# cytron-1.net
KiCad netlist of a schematic drawn in EAGLE
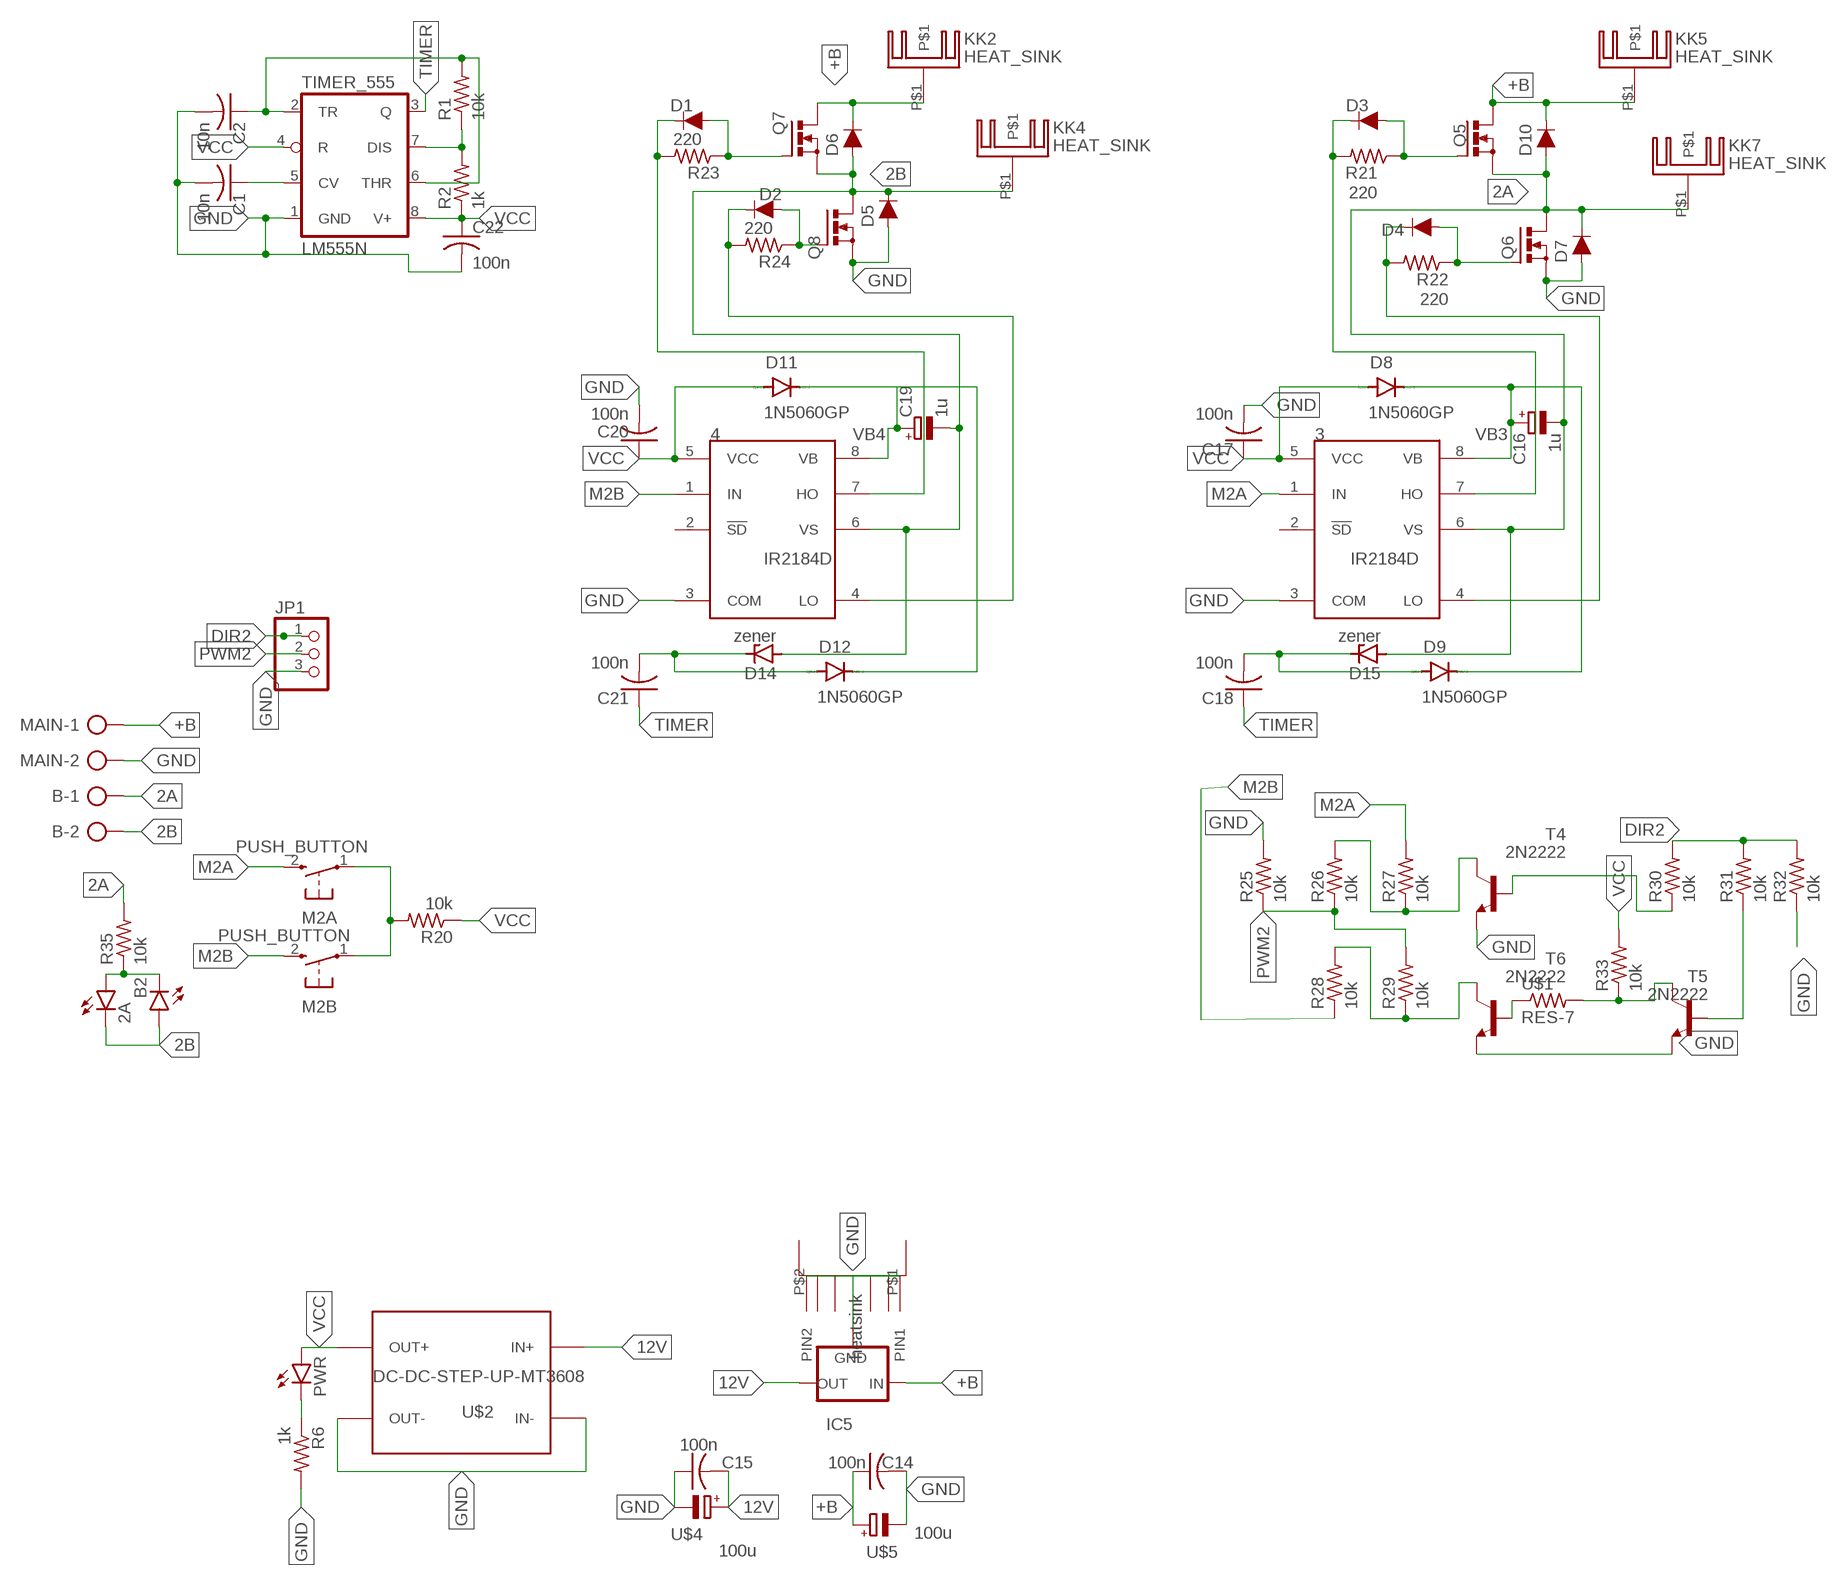
[diagram p0: schematic, sheet 1]

(export (version "E")
  (design (tool "Eeschema 10.0.6"))
  (components
    (comp (ref "2A")
      (value "LED3MM")
      (footprint "eagle-import:LED3MM")
      (libsource (lib "eagle-import") (part "LED3MM"))
    )
    (comp (ref "3")
      (value "IR2184D")
      (footprint "eagle-import:DIL08")
      (libsource (lib "eagle-import") (part "IR2184D"))
    )
    (comp (ref "4")
      (value "IR2184D")
      (footprint "eagle-import:DIL08")
      (libsource (lib "eagle-import") (part "IR2184D"))
    )
    (comp (ref "B")
      (value "ROSTA.POWER")
      (footprint "eagle-import:W239-302")
      (libsource (lib "eagle-import") (part "ROSTA.POWER"))
    )
    (comp (ref "B2")
      (value "LED3MM")
      (footprint "eagle-import:LED3MM")
      (libsource (lib "eagle-import") (part "LED3MM"))
    )
    (comp (ref "C1")
      (value "10n")
      (footprint "eagle-import:C025-025X050")
      (libsource (lib "eagle-import") (part "C-US025-025X050"))
    )
    (comp (ref "C2")
      (value "10n")
      (footprint "eagle-import:C025-025X050")
      (libsource (lib "eagle-import") (part "C-US025-025X050"))
    )
    (comp (ref "C14")
      (value "100n")
      (footprint "eagle-import:C025-025X050")
      (libsource (lib "eagle-import") (part "C-US025-025X050"))
    )
    (comp (ref "C15")
      (value "100n")
      (footprint "eagle-import:C025-025X050")
      (libsource (lib "eagle-import") (part "C-US025-025X050"))
    )
    (comp (ref "C16")
      (value "1u")
      (footprint "eagle-import:E5-5")
      (libsource (lib "eagle-import") (part "CPOL-EUE5-5"))
    )
    (comp (ref "C17")
      (value "100n")
      (footprint "eagle-import:C025-025X050")
      (libsource (lib "eagle-import") (part "C-US025-025X050"))
    )
    (comp (ref "C18")
      (value "100n")
      (footprint "eagle-import:C025-025X050")
      (libsource (lib "eagle-import") (part "C-US025-025X050"))
    )
    (comp (ref "C19")
      (value "1u")
      (footprint "eagle-import:E5-5")
      (libsource (lib "eagle-import") (part "CPOL-EUE5-5"))
    )
    (comp (ref "C20")
      (value "100n")
      (footprint "eagle-import:C025-025X050")
      (libsource (lib "eagle-import") (part "C-US025-025X050"))
    )
    (comp (ref "C21")
      (value "100n")
      (footprint "eagle-import:C025-025X050")
      (libsource (lib "eagle-import") (part "C-US025-025X050"))
    )
    (comp (ref "C22")
      (value "100n")
      (footprint "eagle-import:C025-025X050")
      (libsource (lib "eagle-import") (part "C-US025-025X050"))
    )
    (comp (ref "D1")
      (value "1A/50V/1.1V")
      (footprint "eagle-import:DIODE-1N4001")
      (libsource (lib "eagle-import") (part "DIODE(1A)-PTH"))
    )
    (comp (ref "D2")
      (value "1A/50V/1.1V")
      (footprint "eagle-import:DIODE-1N4001")
      (libsource (lib "eagle-import") (part "DIODE(1A)-PTH"))
    )
    (comp (ref "D3")
      (value "1A/50V/1.1V")
      (footprint "eagle-import:DIODE-1N4001")
      (libsource (lib "eagle-import") (part "DIODE(1A)-PTH"))
    )
    (comp (ref "D4")
      (value "1A/50V/1.1V")
      (footprint "eagle-import:DIODE-1N4001")
      (libsource (lib "eagle-import") (part "DIODE(1A)-PTH"))
    )
    (comp (ref "D5")
      (value "1A/50V/1.1V")
      (footprint "eagle-import:DIODE-1N4001")
      (libsource (lib "eagle-import") (part "DIODE(1A)-PTH"))
    )
    (comp (ref "D6")
      (value "1A/50V/1.1V")
      (footprint "eagle-import:DIODE-1N4001")
      (libsource (lib "eagle-import") (part "DIODE(1A)-PTH"))
    )
    (comp (ref "D7")
      (value "1A/50V/1.1V")
      (footprint "eagle-import:DIODE-1N4001")
      (libsource (lib "eagle-import") (part "DIODE(1A)-PTH"))
    )
    (comp (ref "D8")
      (value "1N5060GP")
      (footprint "eagle-import:DO15-12")
      (libsource (lib "eagle-import") (part "1N5060GP"))
    )
    (comp (ref "D9")
      (value "1N5060GP")
      (footprint "eagle-import:DO15-12")
      (libsource (lib "eagle-import") (part "1N5060GP"))
    )
    (comp (ref "D10")
      (value "1A/50V/1.1V")
      (footprint "eagle-import:DIODE-1N4001")
      (libsource (lib "eagle-import") (part "DIODE(1A)-PTH"))
    )
    (comp (ref "D11")
      (value "1N5060GP")
      (footprint "eagle-import:DO15-12")
      (libsource (lib "eagle-import") (part "1N5060GP"))
    )
    (comp (ref "D12")
      (value "1N5060GP")
      (footprint "eagle-import:DO15-12")
      (libsource (lib "eagle-import") (part "1N5060GP"))
    )
    (comp (ref "D14")
      (value "zener")
      (footprint "eagle-import:SOD81")
      (libsource (lib "eagle-import") (part "BZD23"))
    )
    (comp (ref "D15")
      (value "zener")
      (footprint "eagle-import:SOD81")
      (libsource (lib "eagle-import") (part "BZD23"))
    )
    (comp (ref "IC5")
      (value "78XXL")
      (footprint "eagle-import:78XXL")
      (libsource (lib "eagle-import") (part "78XXL"))
    )
    (comp (ref "JP1")
      (value "PINHD-3_DATA")
      (footprint "eagle-import:1X03_DATA")
      (libsource (lib "eagle-import") (part "PINHD-3_DATA"))
    )
    (comp (ref "KK2")
      (value "HEAT_SINK")
      (footprint "eagle-import:SK95-2M3")
      (libsource (lib "eagle-import") (part "HEAT_SINK"))
    )
    (comp (ref "KK4")
      (value "HEAT_SINK")
      (footprint "eagle-import:SK95-2M3")
      (libsource (lib "eagle-import") (part "HEAT_SINK"))
    )
    (comp (ref "KK5")
      (value "HEAT_SINK")
      (footprint "eagle-import:SK95-2M3")
      (libsource (lib "eagle-import") (part "HEAT_SINK"))
    )
    (comp (ref "KK7")
      (value "HEAT_SINK")
      (footprint "eagle-import:SK95-2M3")
      (libsource (lib "eagle-import") (part "HEAT_SINK"))
    )
    (comp (ref "M2A")
      (value "PUSH_BUTTON")
      (footprint "eagle-import:B3F-10XX")
      (libsource (lib "eagle-import") (part "PUSH_BUTTON"))
    )
    (comp (ref "M2B")
      (value "PUSH_BUTTON")
      (footprint "eagle-import:B3F-10XX")
      (libsource (lib "eagle-import") (part "PUSH_BUTTON"))
    )
    (comp (ref "MAIN")
      (value "ROSTA.POWER")
      (footprint "eagle-import:W239-302")
      (libsource (lib "eagle-import") (part "ROSTA.POWER"))
    )
    (comp (ref "PWR")
      (value "LED5MM")
      (footprint "eagle-import:LED5MM")
      (libsource (lib "eagle-import") (part "LED5MM"))
    )
    (comp (ref "Q5")
      (value "MOSFET_NTO220BV")
      (footprint "eagle-import:TO220BV")
      (libsource (lib "eagle-import") (part "MOSFET_NTO220BV"))
    )
    (comp (ref "Q6")
      (value "MOSFET_NTO220BV")
      (footprint "eagle-import:TO220BV")
      (libsource (lib "eagle-import") (part "MOSFET_NTO220BV"))
    )
    (comp (ref "Q7")
      (value "MOSFET_NTO220BV")
      (footprint "eagle-import:TO220BV")
      (libsource (lib "eagle-import") (part "MOSFET_NTO220BV"))
    )
    (comp (ref "Q8")
      (value "MOSFET_NTO220BV")
      (footprint "eagle-import:TO220BV")
      (libsource (lib "eagle-import") (part "MOSFET_NTO220BV"))
    )
    (comp (ref "R1")
      (value "10k")
      (footprint "eagle-import:0204_7")
      (libsource (lib "eagle-import") (part "R-US_0204/7"))
    )
    (comp (ref "R2")
      (value "1k")
      (footprint "eagle-import:0204_7")
      (libsource (lib "eagle-import") (part "R-US_0204/7"))
    )
    (comp (ref "R6")
      (value "1k")
      (footprint "eagle-import:0204_7")
      (libsource (lib "eagle-import") (part "R-US_0204/7"))
    )
    (comp (ref "R20")
      (value "10k")
      (footprint "eagle-import:0204_7")
      (libsource (lib "eagle-import") (part "R-US_0204/7"))
    )
    (comp (ref "R21")
      (value "220")
      (footprint "eagle-import:0204_7")
      (libsource (lib "eagle-import") (part "R-US_0204/7"))
    )
    (comp (ref "R22")
      (value "220")
      (footprint "eagle-import:0204_7")
      (libsource (lib "eagle-import") (part "R-US_0204/7"))
    )
    (comp (ref "R23")
      (value "220")
      (footprint "eagle-import:0204_7")
      (libsource (lib "eagle-import") (part "R-US_0204/7"))
    )
    (comp (ref "R24")
      (value "220")
      (footprint "eagle-import:0204_7")
      (libsource (lib "eagle-import") (part "R-US_0204/7"))
    )
    (comp (ref "R25")
      (value "10k")
      (footprint "eagle-import:0204_7")
      (libsource (lib "eagle-import") (part "R-US_0204/7"))
    )
    (comp (ref "R26")
      (value "10k")
      (footprint "eagle-import:0204_7")
      (libsource (lib "eagle-import") (part "R-US_0204/7"))
    )
    (comp (ref "R27")
      (value "10k")
      (footprint "eagle-import:0204_7")
      (libsource (lib "eagle-import") (part "R-US_0204/7"))
    )
    (comp (ref "R28")
      (value "10k")
      (footprint "eagle-import:0204_7")
      (libsource (lib "eagle-import") (part "R-US_0204/7"))
    )
    (comp (ref "R29")
      (value "10k")
      (footprint "eagle-import:0204_7")
      (libsource (lib "eagle-import") (part "R-US_0204/7"))
    )
    (comp (ref "R30")
      (value "10k")
      (footprint "eagle-import:0204_7")
      (libsource (lib "eagle-import") (part "R-US_0204/7"))
    )
    (comp (ref "R31")
      (value "10k")
      (footprint "eagle-import:0204_7")
      (libsource (lib "eagle-import") (part "R-US_0204/7"))
    )
    (comp (ref "R32")
      (value "10k")
      (footprint "eagle-import:0204_7")
      (libsource (lib "eagle-import") (part "R-US_0204/7"))
    )
    (comp (ref "R33")
      (value "10k")
      (footprint "eagle-import:0204_7")
      (libsource (lib "eagle-import") (part "R-US_0204/7"))
    )
    (comp (ref "R35")
      (value "10k")
      (footprint "eagle-import:0204_7")
      (libsource (lib "eagle-import") (part "R-US_0204/7"))
    )
    (comp (ref "T4")
      (value "2N2222")
      (footprint "eagle-import:TO18")
      (fields (field (name "SPICEPREFIX") "J"))
      (libsource (lib "eagle-import") (part "2N2222"))
    )
    (comp (ref "T5")
      (value "2N2222")
      (footprint "eagle-import:TO18")
      (fields (field (name "SPICEPREFIX") "J"))
      (libsource (lib "eagle-import") (part "2N2222"))
    )
    (comp (ref "T6")
      (value "2N2222")
      (footprint "eagle-import:TO18")
      (fields (field (name "SPICEPREFIX") "J"))
      (libsource (lib "eagle-import") (part "2N2222"))
    )
    (comp (ref "TIMER_555")
      (value "LM555N")
      (footprint "eagle-import:DIL08")
      (libsource (lib "eagle-import") (part "555NLM"))
    )
    (comp (ref "U$1")
      (value "RES-7")
      (footprint "eagle-import:0204_7")
      (fields (field (name "SPICEPREFIX") "B"))
      (libsource (lib "eagle-import") (part "RES-7"))
    )
    (comp (ref "U$2")
      (value "DC-DC-STEP-UP-MT3608")
      (footprint "eagle-import:DC-DC-STEP-UP-MT3608")
      (libsource (lib "eagle-import") (part "DC-DC-STEP-UP-MT3608"))
    )
    (comp (ref "U$3")
      (value "HEAT-SINK")
      (footprint "eagle-import:HEAT_SINK")
      (libsource (lib "eagle-import") (part "HEAT-SINK"))
    )
    (comp (ref "U$4")
      (value "100u")
      (footprint "eagle-import:E3,5-8")
      (libsource (lib "eagle-import") (part "CAP_POL"))
    )
    (comp (ref "U$5")
      (value "100u")
      (footprint "eagle-import:E3,5-8")
      (libsource (lib "eagle-import") (part "CAP_POL"))
    )
  )
  (nets
    (net (code "1") (name "+B") (class "Default")
      (node (ref "C14") (pin "1") (pinfunction "1_1") (pintype "passive"))
      (node (ref "D10") (pin "C") (pinfunction "C_C") (pintype "passive"))
      (node (ref "D6") (pin "C") (pinfunction "C_C") (pintype "passive"))
      (node (ref "IC5") (pin "IN") (pinfunction "IN_IN") (pintype "input"))
      (node (ref "KK2") (pin "P$1") (pinfunction "P$1_P$1") (pintype "bidirectional"))
      (node (ref "KK5") (pin "P$1") (pinfunction "P$1_P$1") (pintype "bidirectional"))
      (node (ref "MAIN") (pin "1") (pinfunction "KL_1") (pintype "passive"))
      (node (ref "Q5") (pin "D") (pinfunction "D_D") (pintype "passive"))
      (node (ref "Q7") (pin "D") (pinfunction "D_D") (pintype "passive"))
      (node (ref "U$5") (pin "+") (pinfunction "+_+") (pintype "passive"))
    )
    (net (code "2") (name "/VB3") (class "Default")
      (node (ref "3") (pin "8") (pinfunction "VB_8") (pintype "power_in"))
      (node (ref "C16") (pin "+") (pinfunction "+_+") (pintype "passive"))
      (node (ref "D8") (pin "C") (pinfunction "C_C") (pintype "passive"))
      (node (ref "D9") (pin "C") (pinfunction "C_C") (pintype "passive"))
    )
    (net (code "3") (name "/VB4") (class "Default")
      (node (ref "4") (pin "8") (pinfunction "VB_8") (pintype "power_in"))
      (node (ref "C19") (pin "+") (pinfunction "+_+") (pintype "passive"))
      (node (ref "D11") (pin "C") (pinfunction "C_C") (pintype "passive"))
      (node (ref "D12") (pin "C") (pinfunction "C_C") (pintype "passive"))
    )
    (net (code "4") (name "2A") (class "Default")
      (node (ref "3") (pin "6") (pinfunction "VS_6") (pintype "power_in"))
      (node (ref "B") (pin "1") (pinfunction "KL_1") (pintype "passive"))
      (node (ref "C16") (pin "-") (pinfunction "-_-") (pintype "passive"))
      (node (ref "D10") (pin "A") (pinfunction "A_A") (pintype "passive"))
      (node (ref "D15") (pin "A") (pinfunction "A_A") (pintype "passive"))
      (node (ref "D7") (pin "C") (pinfunction "C_C") (pintype "passive"))
      (node (ref "KK7") (pin "P$1") (pinfunction "P$1_P$1") (pintype "bidirectional"))
      (node (ref "Q5") (pin "S") (pinfunction "S_S") (pintype "passive"))
      (node (ref "Q6") (pin "D") (pinfunction "D_D") (pintype "passive"))
      (node (ref "R35") (pin "2") (pinfunction "2_2") (pintype "passive"))
    )
    (net (code "5") (name "2B") (class "Default")
      (node (ref "2A") (pin "K") (pinfunction "C_K") (pintype "passive"))
      (node (ref "4") (pin "6") (pinfunction "VS_6") (pintype "power_in"))
      (node (ref "B") (pin "2") (pinfunction "KL_2") (pintype "passive"))
      (node (ref "B2") (pin "A") (pinfunction "A_A") (pintype "passive"))
      (node (ref "C19") (pin "-") (pinfunction "-_-") (pintype "passive"))
      (node (ref "D14") (pin "A") (pinfunction "A_A") (pintype "passive"))
      (node (ref "D5") (pin "C") (pinfunction "C_C") (pintype "passive"))
      (node (ref "D6") (pin "A") (pinfunction "A_A") (pintype "passive"))
      (node (ref "KK4") (pin "P$1") (pinfunction "P$1_P$1") (pintype "bidirectional"))
      (node (ref "Q7") (pin "S") (pinfunction "S_S") (pintype "passive"))
      (node (ref "Q8") (pin "D") (pinfunction "D_D") (pintype "passive"))
    )
    (net (code "6") (name "12V") (class "Default")
      (node (ref "C15") (pin "2") (pinfunction "2_2") (pintype "passive"))
      (node (ref "IC5") (pin "OUT") (pinfunction "OUT_OUT") (pintype "passive"))
      (node (ref "U$2") (pin "IN+") (pinfunction "IN+_IN+") (pintype "bidirectional"))
      (node (ref "U$4") (pin "+") (pinfunction "+_+") (pintype "passive"))
    )
    (net (code "7") (name "DIR2") (class "Default")
      (node (ref "JP1") (pin "1") (pinfunction "1_1") (pintype "passive"))
      (node (ref "R30") (pin "2") (pinfunction "2_2") (pintype "passive"))
      (node (ref "R31") (pin "2") (pinfunction "2_2") (pintype "passive"))
      (node (ref "R32") (pin "2") (pinfunction "2_2") (pintype "passive"))
    )
    (net (code "8") (name "GND") (class "Default")
      (node (ref "3") (pin "3") (pinfunction "COM_3") (pintype "power_in"))
      (node (ref "4") (pin "3") (pinfunction "COM_3") (pintype "power_in"))
      (node (ref "C1") (pin "2") (pinfunction "2_2") (pintype "passive"))
      (node (ref "C14") (pin "2") (pinfunction "2_2") (pintype "passive"))
      (node (ref "C15") (pin "1") (pinfunction "1_1") (pintype "passive"))
      (node (ref "C17") (pin "2") (pinfunction "2_2") (pintype "passive"))
      (node (ref "C2") (pin "2") (pinfunction "2_2") (pintype "passive"))
      (node (ref "C20") (pin "2") (pinfunction "2_2") (pintype "passive"))
      (node (ref "C22") (pin "2") (pinfunction "2_2") (pintype "passive"))
      (node (ref "D5") (pin "A") (pinfunction "A_A") (pintype "passive"))
      (node (ref "D7") (pin "A") (pinfunction "A_A") (pintype "passive"))
      (node (ref "IC5") (pin "GND") (pinfunction "GND_GND") (pintype "input"))
      (node (ref "JP1") (pin "3") (pinfunction "3_3") (pintype "passive"))
      (node (ref "MAIN") (pin "2") (pinfunction "KL_2") (pintype "passive"))
      (node (ref "Q6") (pin "S") (pinfunction "S_S") (pintype "passive"))
      (node (ref "Q8") (pin "S") (pinfunction "S_S") (pintype "passive"))
      (node (ref "R25") (pin "2") (pinfunction "2_2") (pintype "passive"))
      (node (ref "R32") (pin "1") (pinfunction "1_1") (pintype "passive"))
      (node (ref "R6") (pin "2") (pinfunction "2_2") (pintype "passive"))
      (node (ref "T4") (pin "1") (pinfunction "E_1") (pintype "passive"))
      (node (ref "T5") (pin "1") (pinfunction "E_1") (pintype "passive"))
      (node (ref "T6") (pin "1") (pinfunction "E_1") (pintype "passive"))
      (node (ref "TIMER_555") (pin "1") (pinfunction "GND_1") (pintype "power_in"))
      (node (ref "U$2") (pin "IN-") (pinfunction "IN-_IN-") (pintype "bidirectional"))
      (node (ref "U$2") (pin "OUT-") (pinfunction "OUT-_OUT-") (pintype "bidirectional"))
      (node (ref "U$3") (pin "P$1") (pinfunction "PIN1_P$1") (pintype "bidirectional"))
      (node (ref "U$3") (pin "P$2") (pinfunction "PIN2_P$2") (pintype "bidirectional"))
      (node (ref "U$4") (pin "-") (pinfunction "-_-") (pintype "passive"))
      (node (ref "U$5") (pin "-") (pinfunction "-_-") (pintype "passive"))
    )
    (net (code "9") (name "M2A") (class "Default")
      (node (ref "3") (pin "1") (pinfunction "IN_1") (pintype "input"))
      (node (ref "M2A") (pin "2") (pinfunction "S_2") (pintype "passive"))
      (node (ref "R27") (pin "2") (pinfunction "2_2") (pintype "passive"))
    )
    (net (code "10") (name "M2B") (class "Default")
      (node (ref "4") (pin "1") (pinfunction "IN_1") (pintype "input"))
      (node (ref "M2B") (pin "2") (pinfunction "S_2") (pintype "passive"))
      (node (ref "R28") (pin "1") (pinfunction "1_1") (pintype "passive"))
    )
    (net (code "11") (name "Net-(3-HO)") (class "Default")
      (node (ref "3") (pin "7") (pinfunction "HO_7") (pintype "output"))
      (node (ref "D3") (pin "C") (pinfunction "C_C") (pintype "passive"))
      (node (ref "R21") (pin "2") (pinfunction "2_2") (pintype "passive"))
    )
    (net (code "12") (name "Net-(3-LO)") (class "Default")
      (node (ref "3") (pin "4") (pinfunction "LO_4") (pintype "output"))
      (node (ref "D4") (pin "C") (pinfunction "C_C") (pintype "passive"))
      (node (ref "R22") (pin "2") (pinfunction "2_2") (pintype "passive"))
    )
    (net (code "13") (name "Net-(4-HO)") (class "Default")
      (node (ref "4") (pin "7") (pinfunction "HO_7") (pintype "output"))
      (node (ref "D1") (pin "C") (pinfunction "C_C") (pintype "passive"))
      (node (ref "R23") (pin "2") (pinfunction "2_2") (pintype "passive"))
    )
    (net (code "14") (name "Net-(4-LO)") (class "Default")
      (node (ref "4") (pin "4") (pinfunction "LO_4") (pintype "output"))
      (node (ref "D2") (pin "C") (pinfunction "C_C") (pintype "passive"))
      (node (ref "R24") (pin "2") (pinfunction "2_2") (pintype "passive"))
    )
    (net (code "15") (name "Net-(B2-C)") (class "Default")
      (node (ref "2A") (pin "A") (pinfunction "A_A") (pintype "passive"))
      (node (ref "B2") (pin "K") (pinfunction "C_K") (pintype "passive"))
      (node (ref "R35") (pin "1") (pinfunction "1_1") (pintype "passive"))
    )
    (net (code "16") (name "Net-(C18-Pad2)") (class "Default")
      (node (ref "C18") (pin "2") (pinfunction "2_2") (pintype "passive"))
      (node (ref "D15") (pin "C") (pinfunction "C_C") (pintype "passive"))
      (node (ref "D9") (pin "A") (pinfunction "A_A") (pintype "passive"))
    )
    (net (code "17") (name "Net-(C21-Pad2)") (class "Default")
      (node (ref "C21") (pin "2") (pinfunction "2_2") (pintype "passive"))
      (node (ref "D12") (pin "A") (pinfunction "A_A") (pintype "passive"))
      (node (ref "D14") (pin "C") (pinfunction "C_C") (pintype "passive"))
    )
    (net (code "18") (name "Net-(D1-PadA)") (class "Default")
      (node (ref "D1") (pin "A") (pinfunction "A_A") (pintype "passive"))
      (node (ref "Q7") (pin "G") (pinfunction "G_G") (pintype "passive"))
      (node (ref "R23") (pin "1") (pinfunction "1_1") (pintype "passive"))
    )
    (net (code "19") (name "Net-(D2-PadA)") (class "Default")
      (node (ref "D2") (pin "A") (pinfunction "A_A") (pintype "passive"))
      (node (ref "Q8") (pin "G") (pinfunction "G_G") (pintype "passive"))
      (node (ref "R24") (pin "1") (pinfunction "1_1") (pintype "passive"))
    )
    (net (code "20") (name "Net-(D3-PadA)") (class "Default")
      (node (ref "D3") (pin "A") (pinfunction "A_A") (pintype "passive"))
      (node (ref "Q5") (pin "G") (pinfunction "G_G") (pintype "passive"))
      (node (ref "R21") (pin "1") (pinfunction "1_1") (pintype "passive"))
    )
    (net (code "21") (name "Net-(D4-PadA)") (class "Default")
      (node (ref "D4") (pin "A") (pinfunction "A_A") (pintype "passive"))
      (node (ref "Q6") (pin "G") (pinfunction "G_G") (pintype "passive"))
      (node (ref "R22") (pin "1") (pinfunction "1_1") (pintype "passive"))
    )
    (net (code "22") (name "Net-(M2A-P)") (class "Default")
      (node (ref "M2A") (pin "1") (pinfunction "P_1") (pintype "passive"))
      (node (ref "M2B") (pin "1") (pinfunction "P_1") (pintype "passive"))
      (node (ref "R20") (pin "2") (pinfunction "2_2") (pintype "passive"))
    )
    (net (code "23") (name "Net-(PWR-C)") (class "Default")
      (node (ref "PWR") (pin "K") (pinfunction "C_K") (pintype "passive"))
      (node (ref "R6") (pin "1") (pinfunction "1_1") (pintype "passive"))
    )
    (net (code "24") (name "Net-(T4-B)") (class "Default")
      (node (ref "R30") (pin "1") (pinfunction "1_1") (pintype "passive"))
      (node (ref "T4") (pin "2") (pinfunction "B_2") (pintype "passive"))
    )
    (net (code "25") (name "Net-(T4-C)") (class "Default")
      (node (ref "R26") (pin "2") (pinfunction "2_2") (pintype "passive"))
      (node (ref "R27") (pin "1") (pinfunction "1_1") (pintype "passive"))
      (node (ref "T4") (pin "3") (pinfunction "C_3") (pintype "passive"))
    )
    (net (code "26") (name "Net-(T5-B)") (class "Default")
      (node (ref "R31") (pin "1") (pinfunction "1_1") (pintype "passive"))
      (node (ref "T5") (pin "2") (pinfunction "B_2") (pintype "passive"))
    )
    (net (code "27") (name "Net-(T5-C)") (class "Default")
      (node (ref "R33") (pin "1") (pinfunction "1_1") (pintype "passive"))
      (node (ref "T5") (pin "3") (pinfunction "C_3") (pintype "passive"))
      (node (ref "U$1") (pin "2") (pinfunction "2_2") (pintype "passive"))
    )
    (net (code "28") (name "Net-(T6-B)") (class "Default")
      (node (ref "T6") (pin "2") (pinfunction "B_2") (pintype "passive"))
      (node (ref "U$1") (pin "1") (pinfunction "1_1") (pintype "passive"))
    )
    (net (code "29") (name "Net-(T6-C)") (class "Default")
      (node (ref "R28") (pin "2") (pinfunction "2_2") (pintype "passive"))
      (node (ref "R29") (pin "1") (pinfunction "1_1") (pintype "passive"))
      (node (ref "T6") (pin "3") (pinfunction "C_3") (pintype "passive"))
    )
    (net (code "30") (name "Net-(TIMER_555-CV)") (class "Default")
      (node (ref "C1") (pin "1") (pinfunction "1_1") (pintype "passive"))
      (node (ref "TIMER_555") (pin "5") (pinfunction "CV_5") (pintype "input"))
    )
    (net (code "31") (name "Net-(TIMER_555-DIS)") (class "Default")
      (node (ref "R1") (pin "1") (pinfunction "1_1") (pintype "passive"))
      (node (ref "R2") (pin "2") (pinfunction "2_2") (pintype "passive"))
      (node (ref "TIMER_555") (pin "7") (pinfunction "DIS_7") (pintype "input"))
    )
    (net (code "32") (name "Net-(TIMER_555-THR)") (class "Default")
      (node (ref "C2") (pin "1") (pinfunction "1_1") (pintype "passive"))
      (node (ref "R1") (pin "2") (pinfunction "2_2") (pintype "passive"))
      (node (ref "TIMER_555") (pin "2") (pinfunction "TR_2") (pintype "input"))
      (node (ref "TIMER_555") (pin "6") (pinfunction "THR_6") (pintype "input"))
    )
    (net (code "33") (name "PWM2") (class "Default")
      (node (ref "JP1") (pin "2") (pinfunction "2_2") (pintype "passive"))
      (node (ref "R25") (pin "1") (pinfunction "1_1") (pintype "passive"))
      (node (ref "R26") (pin "1") (pinfunction "1_1") (pintype "passive"))
      (node (ref "R29") (pin "2") (pinfunction "2_2") (pintype "passive"))
    )
    (net (code "34") (name "TIMER") (class "Default")
      (node (ref "C18") (pin "1") (pinfunction "1_1") (pintype "passive"))
      (node (ref "C21") (pin "1") (pinfunction "1_1") (pintype "passive"))
      (node (ref "TIMER_555") (pin "3") (pinfunction "Q_3") (pintype "output"))
    )
    (net (code "35") (name "VCC") (class "Default")
      (node (ref "3") (pin "5") (pinfunction "VCC_5") (pintype "power_in"))
      (node (ref "4") (pin "5") (pinfunction "VCC_5") (pintype "power_in"))
      (node (ref "C17") (pin "1") (pinfunction "1_1") (pintype "passive"))
      (node (ref "C20") (pin "1") (pinfunction "1_1") (pintype "passive"))
      (node (ref "C22") (pin "1") (pinfunction "1_1") (pintype "passive"))
      (node (ref "D11") (pin "A") (pinfunction "A_A") (pintype "passive"))
      (node (ref "D8") (pin "A") (pinfunction "A_A") (pintype "passive"))
      (node (ref "PWR") (pin "A") (pinfunction "A_A") (pintype "passive"))
      (node (ref "R2") (pin "1") (pinfunction "1_1") (pintype "passive"))
      (node (ref "R20") (pin "1") (pinfunction "1_1") (pintype "passive"))
      (node (ref "R33") (pin "2") (pinfunction "2_2") (pintype "passive"))
      (node (ref "TIMER_555") (pin "4") (pinfunction "R_4") (pintype "input"))
      (node (ref "TIMER_555") (pin "8") (pinfunction "V+_8") (pintype "power_in"))
      (node (ref "U$2") (pin "OUT+") (pinfunction "OUT+_OUT+") (pintype "bidirectional"))
    )
    (net (code "36") (name "unconnected-(3-~{SD}-Pad2)") (class "Default")
      (node (ref "3") (pin "2") (pinfunction "~{SD}_2") (pintype "input"))
    )
    (net (code "37") (name "unconnected-(4-~{SD}-Pad2)") (class "Default")
      (node (ref "4") (pin "2") (pinfunction "~{SD}_2") (pintype "input"))
    )
  )
)
